# driver0-3.net
KiCad netlist of a schematic drawn in Altium Designer
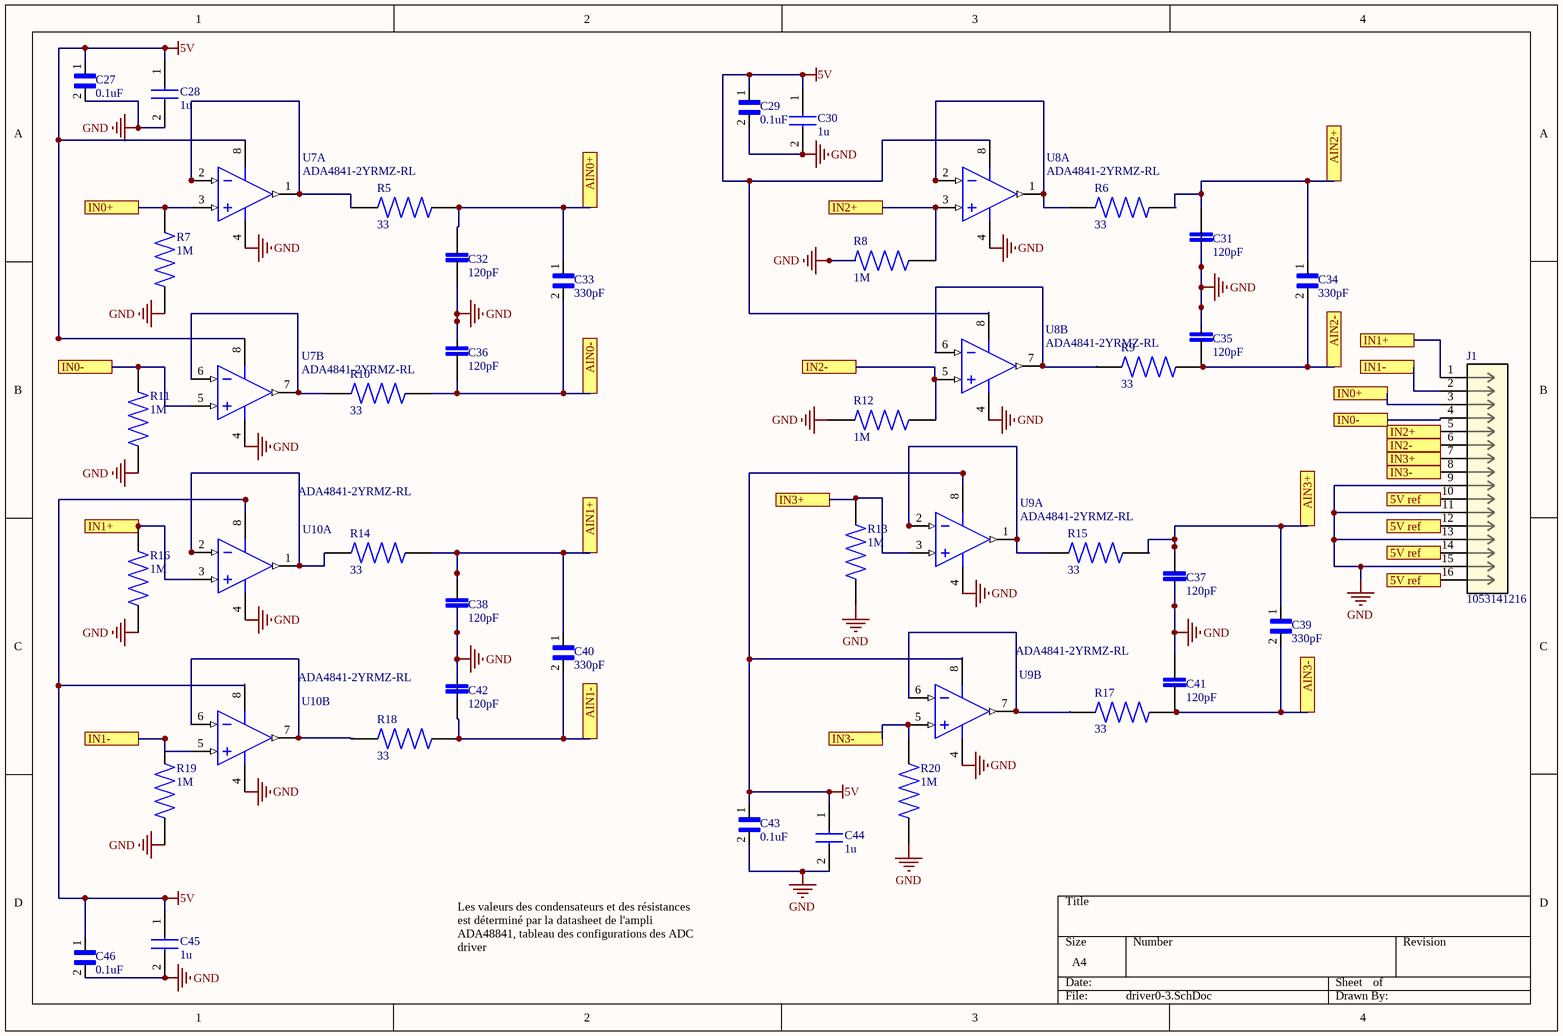
[diagram p0: driver0-3.SchDoc]

(export (version "E")
  (design (tool "Eeschema 10.0.6"))
  (components
    (comp (ref "C27")
      (value "0.1uF")
      (footprint "CAPC1608X90N")
      (description "Cap Ceramic 0.1uF 25V X5R 10% SMD 0603 85ÂÂŽ T/R")
      (fields (field (name "MP") "06033D104KAT2A") (field (name "MF") "{'manufacturer': u'AVX'}"))
      (libsource (lib "GIGUL") (part "06033D104KAT2A"))
    )
    (comp (ref "C28")
      (value "1u")
      (footprint "CAPC1608X90N")
      (description "Capacitor")
      (fields (field (name "MANUFACTURER_PART_NUMBER") "0603YC105MAT4A"))
      (libsource (lib "GIGUL") (part "0603YC105MAT4A"))
    )
    (comp (ref "C29")
      (value "0.1uF")
      (footprint "CAPC1608X90N")
      (description "Cap Ceramic 0.1uF 25V X5R 10% SMD 0603 85ÂÂŽ T/R")
      (fields (field (name "MP") "06033D104KAT2A") (field (name "MF") "{'manufacturer': u'AVX'}"))
      (libsource (lib "GIGUL") (part "06033D104KAT2A"))
    )
    (comp (ref "C30")
      (value "1u")
      (footprint "CAPC1608X90N")
      (description "Capacitor")
      (fields (field (name "MANUFACTURER_PART_NUMBER") "0603YC105MAT4A"))
      (libsource (lib "GIGUL") (part "0603YC105MAT4A"))
    )
    (comp (ref "C31")
      (value "120pF")
      (footprint "CAPC1608X90")
      (description "0603 120 pF 50 V Â±2 % Tolerance C0G/NP0 SMT Multilayer Ceramic Capacitor")
      (fields (field (name "MP") "06035A121GAT2A") (field (name "MF") "{'manufacturer': u'AVX'}"))
      (libsource (lib "GIGUL") (part "06035A121GAT2A"))
    )
    (comp (ref "C32")
      (value "120pF")
      (footprint "CAPC1608X90")
      (description "0603 120 pF 50 V Â±2 % Tolerance C0G/NP0 SMT Multilayer Ceramic Capacitor")
      (fields (field (name "MP") "06035A121GAT2A") (field (name "MF") "{'manufacturer': u'AVX'}"))
      (libsource (lib "GIGUL") (part "06035A121GAT2A"))
    )
    (comp (ref "C33")
      (value "330pF")
      (footprint "CAPC1608X90")
      (description "0603 SMD Ceramic Capacitors 0603 330pF 25volts C0G 2%")
      (fields (field (name "MP") "06033A331GAT2A") (field (name "MF") "{'manufacturer': u'AVX'}"))
      (libsource (lib "GIGUL") (part "Symbol"))
    )
    (comp (ref "C34")
      (value "330pF")
      (footprint "CAPC1608X90")
      (description "0603 SMD Ceramic Capacitors 0603 330pF 25volts C0G 2%")
      (fields (field (name "MP") "06033A331GAT2A") (field (name "MF") "{'manufacturer': u'AVX'}"))
      (libsource (lib "GIGUL") (part "Symbol"))
    )
    (comp (ref "C35")
      (value "120pF")
      (footprint "CAPC1608X90")
      (description "0603 120 pF 50 V Â±2 % Tolerance C0G/NP0 SMT Multilayer Ceramic Capacitor")
      (fields (field (name "MP") "06035A121GAT2A") (field (name "MF") "{'manufacturer': u'AVX'}"))
      (libsource (lib "GIGUL") (part "06035A121GAT2A"))
    )
    (comp (ref "C36")
      (value "120pF")
      (footprint "CAPC1608X90")
      (description "0603 120 pF 50 V Â±2 % Tolerance C0G/NP0 SMT Multilayer Ceramic Capacitor")
      (fields (field (name "MP") "06035A121GAT2A") (field (name "MF") "{'manufacturer': u'AVX'}"))
      (libsource (lib "GIGUL") (part "06035A121GAT2A"))
    )
    (comp (ref "C37")
      (value "120pF")
      (footprint "CAPC1608X90")
      (description "0603 120 pF 50 V Â±2 % Tolerance C0G/NP0 SMT Multilayer Ceramic Capacitor")
      (fields (field (name "MP") "06035A121GAT2A") (field (name "MF") "{'manufacturer': u'AVX'}"))
      (libsource (lib "GIGUL") (part "06035A121GAT2A"))
    )
    (comp (ref "C38")
      (value "120pF")
      (footprint "CAPC1608X90")
      (description "0603 120 pF 50 V Â±2 % Tolerance C0G/NP0 SMT Multilayer Ceramic Capacitor")
      (fields (field (name "MP") "06035A121GAT2A") (field (name "MF") "{'manufacturer': u'AVX'}"))
      (libsource (lib "GIGUL") (part "06035A121GAT2A"))
    )
    (comp (ref "C39")
      (value "330pF")
      (footprint "CAPC1608X90")
      (description "0603 SMD Ceramic Capacitors 0603 330pF 25volts C0G 2%")
      (fields (field (name "MP") "06033A331GAT2A") (field (name "MF") "{'manufacturer': u'AVX'}"))
      (libsource (lib "GIGUL") (part "Symbol"))
    )
    (comp (ref "C40")
      (value "330pF")
      (footprint "CAPC1608X90")
      (description "0603 SMD Ceramic Capacitors 0603 330pF 25volts C0G 2%")
      (fields (field (name "MP") "06033A331GAT2A") (field (name "MF") "{'manufacturer': u'AVX'}"))
      (libsource (lib "GIGUL") (part "Symbol"))
    )
    (comp (ref "C41")
      (value "120pF")
      (footprint "CAPC1608X90")
      (description "0603 120 pF 50 V Â±2 % Tolerance C0G/NP0 SMT Multilayer Ceramic Capacitor")
      (fields (field (name "MP") "06035A121GAT2A") (field (name "MF") "{'manufacturer': u'AVX'}"))
      (libsource (lib "GIGUL") (part "06035A121GAT2A"))
    )
    (comp (ref "C42")
      (value "120pF")
      (footprint "CAPC1608X90")
      (description "0603 120 pF 50 V Â±2 % Tolerance C0G/NP0 SMT Multilayer Ceramic Capacitor")
      (fields (field (name "MP") "06035A121GAT2A") (field (name "MF") "{'manufacturer': u'AVX'}"))
      (libsource (lib "GIGUL") (part "06035A121GAT2A"))
    )
    (comp (ref "C43")
      (value "0.1uF")
      (footprint "CAPC1608X90N")
      (description "Cap Ceramic 0.1uF 25V X5R 10% SMD 0603 85ÂÂŽ T/R")
      (fields (field (name "MP") "06033D104KAT2A") (field (name "MF") "{'manufacturer': u'AVX'}"))
      (libsource (lib "GIGUL") (part "06033D104KAT2A"))
    )
    (comp (ref "C44")
      (value "1u")
      (footprint "CAPC1608X90N")
      (description "Capacitor")
      (fields (field (name "MANUFACTURER_PART_NUMBER") "0603YC105MAT4A"))
      (libsource (lib "GIGUL") (part "0603YC105MAT4A"))
    )
    (comp (ref "C45")
      (value "1u")
      (footprint "CAPC1608X90N")
      (description "Capacitor")
      (fields (field (name "MANUFACTURER_PART_NUMBER") "0603YC105MAT4A"))
      (libsource (lib "GIGUL") (part "0603YC105MAT4A"))
    )
    (comp (ref "C46")
      (value "0.1uF")
      (footprint "CAPC1608X90N")
      (description "Cap Ceramic 0.1uF 25V X5R 10% SMD 0603 85ÂÂŽ T/R")
      (fields (field (name "MP") "06033D104KAT2A") (field (name "MF") "{'manufacturer': u'AVX'}"))
      (libsource (lib "GIGUL") (part "06033D104KAT2A"))
    )
    (comp (ref "J1")
      (value "1053141216")
      (footprint "CON_1053141216")
      (description "No Description Available")
      (fields (field (name "COPYRIGHT") "Copyright (C) 2021 Ultra Librarian. All rights reserved."))
      (libsource (lib "GIGUL") (part "1053141216"))
    )
    (comp (ref "R5")
      (value "33")
      (footprint "RESC1608X55N")
      (description "RES SMD 33 OHM 0.1% 1/10W 0603")
      (fields (field (name "MP") "RT0603BRD0733RL") (field (name "MF") "{'manufacturer': u'Yageo'}"))
      (libsource (lib "") (part "Symbol_1"))
    )
    (comp (ref "R6")
      (value "33")
      (footprint "RESC1608X55N")
      (description "RES SMD 33 OHM 0.1% 1/10W 0603")
      (fields (field (name "MP") "RT0603BRD0733RL") (field (name "MF") "{'manufacturer': u'Yageo'}"))
      (libsource (lib "") (part "Symbol_1"))
    )
    (comp (ref "R7")
      (value "1M")
      (footprint "RESC1608X55N")
      (fields (field (name "MP") "RT0603DRD071ML") (field (name "MF") "{'manufacturer': u'Yageo'}"))
      (libsource (lib "") (part "Symbol_1"))
    )
    (comp (ref "R8")
      (value "1M")
      (footprint "RESC1608X55N")
      (fields (field (name "MP") "RT0603DRD071ML") (field (name "MF") "{'manufacturer': u'Yageo'}"))
      (libsource (lib "") (part "Symbol_1"))
    )
    (comp (ref "R9")
      (value "33")
      (footprint "RESC1608X55N")
      (description "RES SMD 33 OHM 0.1% 1/10W 0603")
      (fields (field (name "MP") "RT0603BRD0733RL") (field (name "MF") "{'manufacturer': u'Yageo'}"))
      (libsource (lib "") (part "Symbol_1"))
    )
    (comp (ref "R10")
      (value "33")
      (footprint "RESC1608X55N")
      (description "RES SMD 33 OHM 0.1% 1/10W 0603")
      (fields (field (name "MP") "RT0603BRD0733RL") (field (name "MF") "{'manufacturer': u'Yageo'}"))
      (libsource (lib "") (part "Symbol_1"))
    )
    (comp (ref "R11")
      (value "1M")
      (footprint "RESC1608X55N")
      (fields (field (name "MP") "RT0603DRD071ML") (field (name "MF") "{'manufacturer': u'Yageo'}"))
      (libsource (lib "") (part "Symbol_1"))
    )
    (comp (ref "R12")
      (value "1M")
      (footprint "RESC1608X55N")
      (fields (field (name "MP") "RT0603DRD071ML") (field (name "MF") "{'manufacturer': u'Yageo'}"))
      (libsource (lib "") (part "Symbol_1"))
    )
    (comp (ref "R13")
      (value "1M")
      (footprint "RESC1608X55N")
      (fields (field (name "MP") "RT0603DRD071ML") (field (name "MF") "{'manufacturer': u'Yageo'}"))
      (libsource (lib "") (part "Symbol_1"))
    )
    (comp (ref "R14")
      (value "33")
      (footprint "RESC1608X55N")
      (description "RES SMD 33 OHM 0.1% 1/10W 0603")
      (fields (field (name "MP") "RT0603BRD0733RL") (field (name "MF") "{'manufacturer': u'Yageo'}"))
      (libsource (lib "") (part "Symbol_1"))
    )
    (comp (ref "R15")
      (value "33")
      (footprint "RESC1608X55N")
      (description "RES SMD 33 OHM 0.1% 1/10W 0603")
      (fields (field (name "MP") "RT0603BRD0733RL") (field (name "MF") "{'manufacturer': u'Yageo'}"))
      (libsource (lib "") (part "Symbol_1"))
    )
    (comp (ref "R16")
      (value "1M")
      (footprint "RESC1608X55N")
      (fields (field (name "MP") "RT0603DRD071ML") (field (name "MF") "{'manufacturer': u'Yageo'}"))
      (libsource (lib "") (part "Symbol_1"))
    )
    (comp (ref "R17")
      (value "33")
      (footprint "RESC1608X55N")
      (description "RES SMD 33 OHM 0.1% 1/10W 0603")
      (fields (field (name "MP") "RT0603BRD0733RL") (field (name "MF") "{'manufacturer': u'Yageo'}"))
      (libsource (lib "") (part "Symbol_1"))
    )
    (comp (ref "R18")
      (value "33")
      (footprint "RESC1608X55N")
      (description "RES SMD 33 OHM 0.1% 1/10W 0603")
      (fields (field (name "MP") "RT0603BRD0733RL") (field (name "MF") "{'manufacturer': u'Yageo'}"))
      (libsource (lib "") (part "Symbol_1"))
    )
    (comp (ref "R19")
      (value "1M")
      (footprint "RESC1608X55N")
      (fields (field (name "MP") "RT0603DRD071ML") (field (name "MF") "{'manufacturer': u'Yageo'}"))
      (libsource (lib "") (part "Symbol_1"))
    )
    (comp (ref "R20")
      (value "1M")
      (footprint "RESC1608X55N")
      (fields (field (name "MP") "RT0603DRD071ML") (field (name "MF") "{'manufacturer': u'Yageo'}"))
      (libsource (lib "") (part "Symbol_1"))
    )
    (comp (ref "U7")
      (value "ADA4841-2YRMZ-RL")
      (footprint "ADI-RM-8_M")
      (fields (field (name "MANUFACTURER") "Analog Devices") (field (name "GENERIC PART NUMBER") "ADA4841-2"))
      (libsource (lib "GIGUL") (part "CMP-0384-01677-1"))
    )
    (comp (ref "U8")
      (value "ADA4841-2YRMZ-RL")
      (footprint "ADI-RM-8_M")
      (fields (field (name "MANUFACTURER") "Analog Devices") (field (name "GENERIC PART NUMBER") "ADA4841-2"))
      (libsource (lib "GIGUL") (part "CMP-0384-01677-1"))
    )
    (comp (ref "U9")
      (value "ADA4841-2YRMZ-RL")
      (footprint "ADI-RM-8_M")
      (fields (field (name "MANUFACTURER") "Analog Devices") (field (name "GENERIC PART NUMBER") "ADA4841-2"))
      (libsource (lib "GIGUL") (part "CMP-0384-01677-1"))
    )
    (comp (ref "U10")
      (value "ADA4841-2YRMZ-RL")
      (footprint "ADI-RM-8_M")
      (fields (field (name "MANUFACTURER") "Analog Devices") (field (name "GENERIC PART NUMBER") "ADA4841-2"))
      (libsource (lib "GIGUL") (part "CMP-0384-01677-1"))
    )
  )
  (nets
    (net (code "1") (name "/5V ref") (class "Default")
      (node (ref "J1") (pin "10") (pinfunction "10_10") (pintype "passive"))
      (node (ref "J1") (pin "12") (pinfunction "12_12") (pintype "passive"))
      (node (ref "J1") (pin "14") (pinfunction "14_14") (pintype "passive"))
      (node (ref "J1") (pin "16") (pinfunction "16_16") (pintype "passive"))
    )
    (net (code "2") (name "/AIN0+") (class "Default")
      (node (ref "C32") (pin "2") (pinfunction "2_2") (pintype "passive"))
      (node (ref "C33") (pin "1") (pinfunction "1_1") (pintype "passive"))
      (node (ref "R5") (pin "2") (pinfunction "2_2") (pintype "passive"))
    )
    (net (code "3") (name "/AIN0-") (class "Default")
      (node (ref "C33") (pin "2") (pinfunction "2_2") (pintype "passive"))
      (node (ref "C36") (pin "1") (pinfunction "1_1") (pintype "passive"))
      (node (ref "R10") (pin "2") (pinfunction "2_2") (pintype "passive"))
    )
    (net (code "4") (name "/AIN1+") (class "Default")
      (node (ref "C38") (pin "2") (pinfunction "2_2") (pintype "passive"))
      (node (ref "C40") (pin "1") (pinfunction "1_1") (pintype "passive"))
      (node (ref "R14") (pin "2") (pinfunction "2_2") (pintype "passive"))
    )
    (net (code "5") (name "/AIN1-") (class "Default")
      (node (ref "C40") (pin "2") (pinfunction "2_2") (pintype "passive"))
      (node (ref "C42") (pin "1") (pinfunction "1_1") (pintype "passive"))
      (node (ref "R18") (pin "2") (pinfunction "2_2") (pintype "passive"))
    )
    (net (code "6") (name "/AIN2+") (class "Default")
      (node (ref "C31") (pin "2") (pinfunction "2_2") (pintype "passive"))
      (node (ref "C34") (pin "1") (pinfunction "1_1") (pintype "passive"))
      (node (ref "R6") (pin "2") (pinfunction "2_2") (pintype "passive"))
    )
    (net (code "7") (name "/AIN2-") (class "Default")
      (node (ref "C34") (pin "2") (pinfunction "2_2") (pintype "passive"))
      (node (ref "C35") (pin "1") (pinfunction "1_1") (pintype "passive"))
      (node (ref "R9") (pin "2") (pinfunction "2_2") (pintype "passive"))
    )
    (net (code "8") (name "/AIN3+") (class "Default")
      (node (ref "C37") (pin "2") (pinfunction "2_2") (pintype "passive"))
      (node (ref "C39") (pin "1") (pinfunction "1_1") (pintype "passive"))
      (node (ref "R15") (pin "2") (pinfunction "2_2") (pintype "passive"))
    )
    (net (code "9") (name "/AIN3-") (class "Default")
      (node (ref "C39") (pin "2") (pinfunction "2_2") (pintype "passive"))
      (node (ref "C41") (pin "1") (pinfunction "1_1") (pintype "passive"))
      (node (ref "R17") (pin "2") (pinfunction "2_2") (pintype "passive"))
    )
    (net (code "10") (name "/IN0+") (class "Default")
      (node (ref "J1") (pin "3") (pinfunction "3_3") (pintype "passive"))
      (node (ref "R7") (pin "2") (pinfunction "2_2") (pintype "passive"))
      (node (ref "U7") (pin "3") (pinfunction "+IN_1_3") (pintype "input"))
    )
    (net (code "11") (name "/IN0-") (class "Default")
      (node (ref "J1") (pin "4") (pinfunction "4_4") (pintype "passive"))
      (node (ref "R11") (pin "2") (pinfunction "2_2") (pintype "passive"))
      (node (ref "U7") (pin "5") (pinfunction "+IN_2_5") (pintype "input"))
    )
    (net (code "12") (name "/IN1+") (class "Default")
      (node (ref "J1") (pin "1") (pinfunction "1_1") (pintype "passive"))
      (node (ref "R16") (pin "2") (pinfunction "2_2") (pintype "passive"))
      (node (ref "U10") (pin "3") (pinfunction "+IN_1_3") (pintype "input"))
    )
    (net (code "13") (name "/IN1-") (class "Default")
      (node (ref "J1") (pin "2") (pinfunction "2_2") (pintype "passive"))
      (node (ref "R19") (pin "2") (pinfunction "2_2") (pintype "passive"))
      (node (ref "U10") (pin "5") (pinfunction "+IN_2_5") (pintype "input"))
    )
    (net (code "14") (name "/IN2+") (class "Default")
      (node (ref "J1") (pin "5") (pinfunction "5_5") (pintype "passive"))
      (node (ref "R8") (pin "1") (pinfunction "1_1") (pintype "passive"))
      (node (ref "U8") (pin "3") (pinfunction "+IN_1_3") (pintype "input"))
    )
    (net (code "15") (name "/IN2-") (class "Default")
      (node (ref "J1") (pin "6") (pinfunction "6_6") (pintype "passive"))
      (node (ref "R12") (pin "1") (pinfunction "1_1") (pintype "passive"))
      (node (ref "U8") (pin "5") (pinfunction "+IN_2_5") (pintype "input"))
    )
    (net (code "16") (name "/IN3+") (class "Default")
      (node (ref "J1") (pin "7") (pinfunction "7_7") (pintype "passive"))
      (node (ref "R13") (pin "2") (pinfunction "2_2") (pintype "passive"))
      (node (ref "U9") (pin "3") (pinfunction "+IN_1_3") (pintype "input"))
    )
    (net (code "17") (name "/IN3-") (class "Default")
      (node (ref "J1") (pin "8") (pinfunction "8_8") (pintype "passive"))
      (node (ref "R20") (pin "2") (pinfunction "2_2") (pintype "passive"))
      (node (ref "U9") (pin "5") (pinfunction "+IN_2_5") (pintype "input"))
    )
    (net (code "18") (name "5V") (class "Default")
      (node (ref "C27") (pin "1") (pinfunction "1_1") (pintype "passive"))
      (node (ref "C28") (pin "1") (pinfunction "1_1") (pintype "passive"))
      (node (ref "C29") (pin "1") (pinfunction "1_1") (pintype "passive"))
      (node (ref "C30") (pin "1") (pinfunction "1_1") (pintype "passive"))
      (node (ref "C43") (pin "1") (pinfunction "1_1") (pintype "passive"))
      (node (ref "C44") (pin "1") (pinfunction "1_1") (pintype "passive"))
      (node (ref "C45") (pin "1") (pinfunction "1_1") (pintype "passive"))
      (node (ref "C46") (pin "1") (pinfunction "1_1") (pintype "passive"))
      (node (ref "U10") (pin "8") (pinfunction "+VS_8") (pintype "power_in"))
      (node (ref "U7") (pin "8") (pinfunction "+VS_8") (pintype "power_in"))
      (node (ref "U8") (pin "8") (pinfunction "+VS_8") (pintype "power_in"))
      (node (ref "U9") (pin "8") (pinfunction "+VS_8") (pintype "power_in"))
    )
    (net (code "19") (name "GND") (class "Default")
      (node (ref "C27") (pin "2") (pinfunction "2_2") (pintype "passive"))
      (node (ref "C28") (pin "2") (pinfunction "2_2") (pintype "passive"))
      (node (ref "C29") (pin "2") (pinfunction "2_2") (pintype "passive"))
      (node (ref "C30") (pin "2") (pinfunction "2_2") (pintype "passive"))
      (node (ref "C31") (pin "1") (pinfunction "1_1") (pintype "passive"))
      (node (ref "C32") (pin "1") (pinfunction "1_1") (pintype "passive"))
      (node (ref "C35") (pin "2") (pinfunction "2_2") (pintype "passive"))
      (node (ref "C36") (pin "2") (pinfunction "2_2") (pintype "passive"))
      (node (ref "C37") (pin "1") (pinfunction "1_1") (pintype "passive"))
      (node (ref "C38") (pin "1") (pinfunction "1_1") (pintype "passive"))
      (node (ref "C41") (pin "2") (pinfunction "2_2") (pintype "passive"))
      (node (ref "C42") (pin "2") (pinfunction "2_2") (pintype "passive"))
      (node (ref "C43") (pin "2") (pinfunction "2_2") (pintype "passive"))
      (node (ref "C44") (pin "2") (pinfunction "2_2") (pintype "passive"))
      (node (ref "C45") (pin "2") (pinfunction "2_2") (pintype "passive"))
      (node (ref "C46") (pin "2") (pinfunction "2_2") (pintype "passive"))
      (node (ref "J1") (pin "11") (pinfunction "11_11") (pintype "passive"))
      (node (ref "J1") (pin "13") (pinfunction "13_13") (pintype "passive"))
      (node (ref "J1") (pin "15") (pinfunction "15_15") (pintype "passive"))
      (node (ref "J1") (pin "9") (pinfunction "9_9") (pintype "passive"))
      (node (ref "R11") (pin "1") (pinfunction "1_1") (pintype "passive"))
      (node (ref "R12") (pin "2") (pinfunction "2_2") (pintype "passive"))
      (node (ref "R13") (pin "1") (pinfunction "1_1") (pintype "passive"))
      (node (ref "R16") (pin "1") (pinfunction "1_1") (pintype "passive"))
      (node (ref "R19") (pin "1") (pinfunction "1_1") (pintype "passive"))
      (node (ref "R20") (pin "1") (pinfunction "1_1") (pintype "passive"))
      (node (ref "R7") (pin "1") (pinfunction "1_1") (pintype "passive"))
      (node (ref "R8") (pin "2") (pinfunction "2_2") (pintype "passive"))
      (node (ref "U10") (pin "4") (pinfunction "-VS_4") (pintype "power_in"))
      (node (ref "U7") (pin "4") (pinfunction "-VS_4") (pintype "power_in"))
      (node (ref "U8") (pin "4") (pinfunction "-VS_4") (pintype "power_in"))
      (node (ref "U9") (pin "4") (pinfunction "-VS_4") (pintype "power_in"))
    )
    (net (code "20") (name "Net-(U7A--IN_1)") (class "Default")
      (node (ref "R5") (pin "1") (pinfunction "1_1") (pintype "passive"))
      (node (ref "U7") (pin "1") (pinfunction "OUT_1_1") (pintype "output"))
      (node (ref "U7") (pin "2") (pinfunction "-IN_1_2") (pintype "input"))
    )
    (net (code "21") (name "Net-(U7B--IN_2)") (class "Default")
      (node (ref "R10") (pin "1") (pinfunction "1_1") (pintype "passive"))
      (node (ref "U7") (pin "6") (pinfunction "-IN_2_6") (pintype "input"))
      (node (ref "U7") (pin "7") (pinfunction "OUT_2_7") (pintype "output"))
    )
    (net (code "22") (name "Net-(U8A--IN_1)") (class "Default")
      (node (ref "R6") (pin "1") (pinfunction "1_1") (pintype "passive"))
      (node (ref "U8") (pin "1") (pinfunction "OUT_1_1") (pintype "output"))
      (node (ref "U8") (pin "2") (pinfunction "-IN_1_2") (pintype "input"))
    )
    (net (code "23") (name "Net-(U8B--IN_2)") (class "Default")
      (node (ref "R9") (pin "1") (pinfunction "1_1") (pintype "passive"))
      (node (ref "U8") (pin "6") (pinfunction "-IN_2_6") (pintype "input"))
      (node (ref "U8") (pin "7") (pinfunction "OUT_2_7") (pintype "output"))
    )
    (net (code "24") (name "Net-(U9A--IN_1)") (class "Default")
      (node (ref "R15") (pin "1") (pinfunction "1_1") (pintype "passive"))
      (node (ref "U9") (pin "1") (pinfunction "OUT_1_1") (pintype "output"))
      (node (ref "U9") (pin "2") (pinfunction "-IN_1_2") (pintype "input"))
    )
    (net (code "25") (name "Net-(U9B--IN_2)") (class "Default")
      (node (ref "R17") (pin "1") (pinfunction "1_1") (pintype "passive"))
      (node (ref "U9") (pin "6") (pinfunction "-IN_2_6") (pintype "input"))
      (node (ref "U9") (pin "7") (pinfunction "OUT_2_7") (pintype "output"))
    )
    (net (code "26") (name "Net-(U10A--IN_1)") (class "Default")
      (node (ref "R14") (pin "1") (pinfunction "1_1") (pintype "passive"))
      (node (ref "U10") (pin "1") (pinfunction "OUT_1_1") (pintype "output"))
      (node (ref "U10") (pin "2") (pinfunction "-IN_1_2") (pintype "input"))
    )
    (net (code "27") (name "Net-(U10B--IN_2)") (class "Default")
      (node (ref "R18") (pin "1") (pinfunction "1_1") (pintype "passive"))
      (node (ref "U10") (pin "6") (pinfunction "-IN_2_6") (pintype "input"))
      (node (ref "U10") (pin "7") (pinfunction "OUT_2_7") (pintype "output"))
    )
  )
)
